# bozina.net
KiCad netlist of a schematic drawn in EAGLE
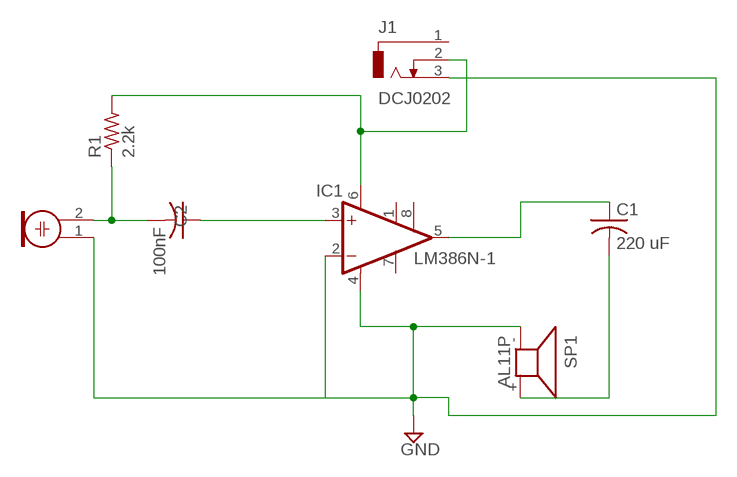
[diagram p0: schematic, sheet 1]

(export (version "E")
  (design (tool "Eeschema 10.0.6"))
  (components
    (comp (ref "C1")
      (value "220 uF")
      (footprint "eagle-import:C025-024X044")
      (libsource (lib "eagle-import") (part "C-US025-024X044"))
    )
    (comp (ref "C2")
      (value "100nF")
      (footprint "eagle-import:C025-024X044")
      (libsource (lib "eagle-import") (part "C-US025-024X044"))
    )
    (comp (ref "IC1")
      (value "LM386N-1")
      (footprint "eagle-import:DIL08")
      (libsource (lib "eagle-import") (part "LM386?-N1"))
    )
    (comp (ref "J1")
      (value "DCJ0202")
      (footprint "eagle-import:DCJ0202")
      (libsource (lib "eagle-import") (part "DCJ0202"))
    )
    (comp (ref "M1")
      (value "ELECTRET_MICROPHON-F6050AP")
      (footprint "eagle-import:F6050AP")
      (libsource (lib "eagle-import") (part "ELECTRET_MICROPHON-F6050AP"))
    )
    (comp (ref "R1")
      (value "2.2k")
      (footprint "eagle-import:0204_5")
      (fields (field (name "SPICEPREFIX") "2.2k"))
      (libsource (lib "eagle-import") (part "R-US_0204/5"))
    )
    (comp (ref "SP1")
      (value "AL11P")
      (footprint "eagle-import:AL11P")
      (libsource (lib "eagle-import") (part "AL11P"))
    )
  )
  (nets
    (net (code "1") (name "GND") (class "Default")
      (node (ref "IC1") (pin "2") (pinfunction "-IN_2") (pintype "input"))
      (node (ref "IC1") (pin "4") (pinfunction "GND_4") (pintype "power_in"))
      (node (ref "J1") (pin "3") (pinfunction "3_3") (pintype "passive"))
      (node (ref "M1") (pin "1") (pinfunction "1_1") (pintype "passive"))
      (node (ref "SP1") (pin "-") (pinfunction "1_-") (pintype "passive"))
    )
    (net (code "2") (name "Net-(C2-Pad2)") (class "Default")
      (node (ref "C2") (pin "2") (pinfunction "2_2") (pintype "passive"))
      (node (ref "M1") (pin "2") (pinfunction "2_2") (pintype "passive"))
      (node (ref "R1") (pin "1") (pinfunction "1_1") (pintype "passive"))
    )
    (net (code "3") (name "Net-(IC1-+IN)") (class "Default")
      (node (ref "C2") (pin "1") (pinfunction "1_1") (pintype "passive"))
      (node (ref "IC1") (pin "3") (pinfunction "+IN_3") (pintype "input"))
    )
    (net (code "4") (name "Net-(IC1-OUT)") (class "Default")
      (node (ref "C1") (pin "1") (pinfunction "1_1") (pintype "passive"))
      (node (ref "IC1") (pin "5") (pinfunction "OUT_5") (pintype "output"))
    )
    (net (code "5") (name "Net-(IC1-VS)") (class "Default")
      (node (ref "IC1") (pin "6") (pinfunction "VS_6") (pintype "power_in"))
      (node (ref "J1") (pin "2") (pinfunction "2_2") (pintype "passive"))
      (node (ref "R1") (pin "2") (pinfunction "2_2") (pintype "passive"))
    )
    (net (code "6") (name "Net-(SP1-2)") (class "Default")
      (node (ref "C1") (pin "2") (pinfunction "2_2") (pintype "passive"))
      (node (ref "SP1") (pin "+") (pinfunction "2_+") (pintype "passive"))
    )
    (net (code "7") (name "unconnected-(IC1-BYPASS-Pad7)") (class "Default")
      (node (ref "IC1") (pin "7") (pinfunction "BYPASS_7") (pintype "passive"))
    )
    (net (code "8") (name "unconnected-(IC1-GAIN-Pad1)") (class "Default")
      (node (ref "IC1") (pin "1") (pinfunction "GAIN_1") (pintype "passive"))
    )
    (net (code "9") (name "unconnected-(IC1-GAIN-Pad8)") (class "Default")
      (node (ref "IC1") (pin "8") (pinfunction "GAIN_8") (pintype "passive"))
    )
    (net (code "10") (name "unconnected-(J1-Pad1)") (class "Default")
      (node (ref "J1") (pin "1") (pinfunction "1_1") (pintype "passive"))
    )
  )
)
